# ESP_SCH_2_IMU.net
KiCad netlist of a schematic drawn in EasyEDA
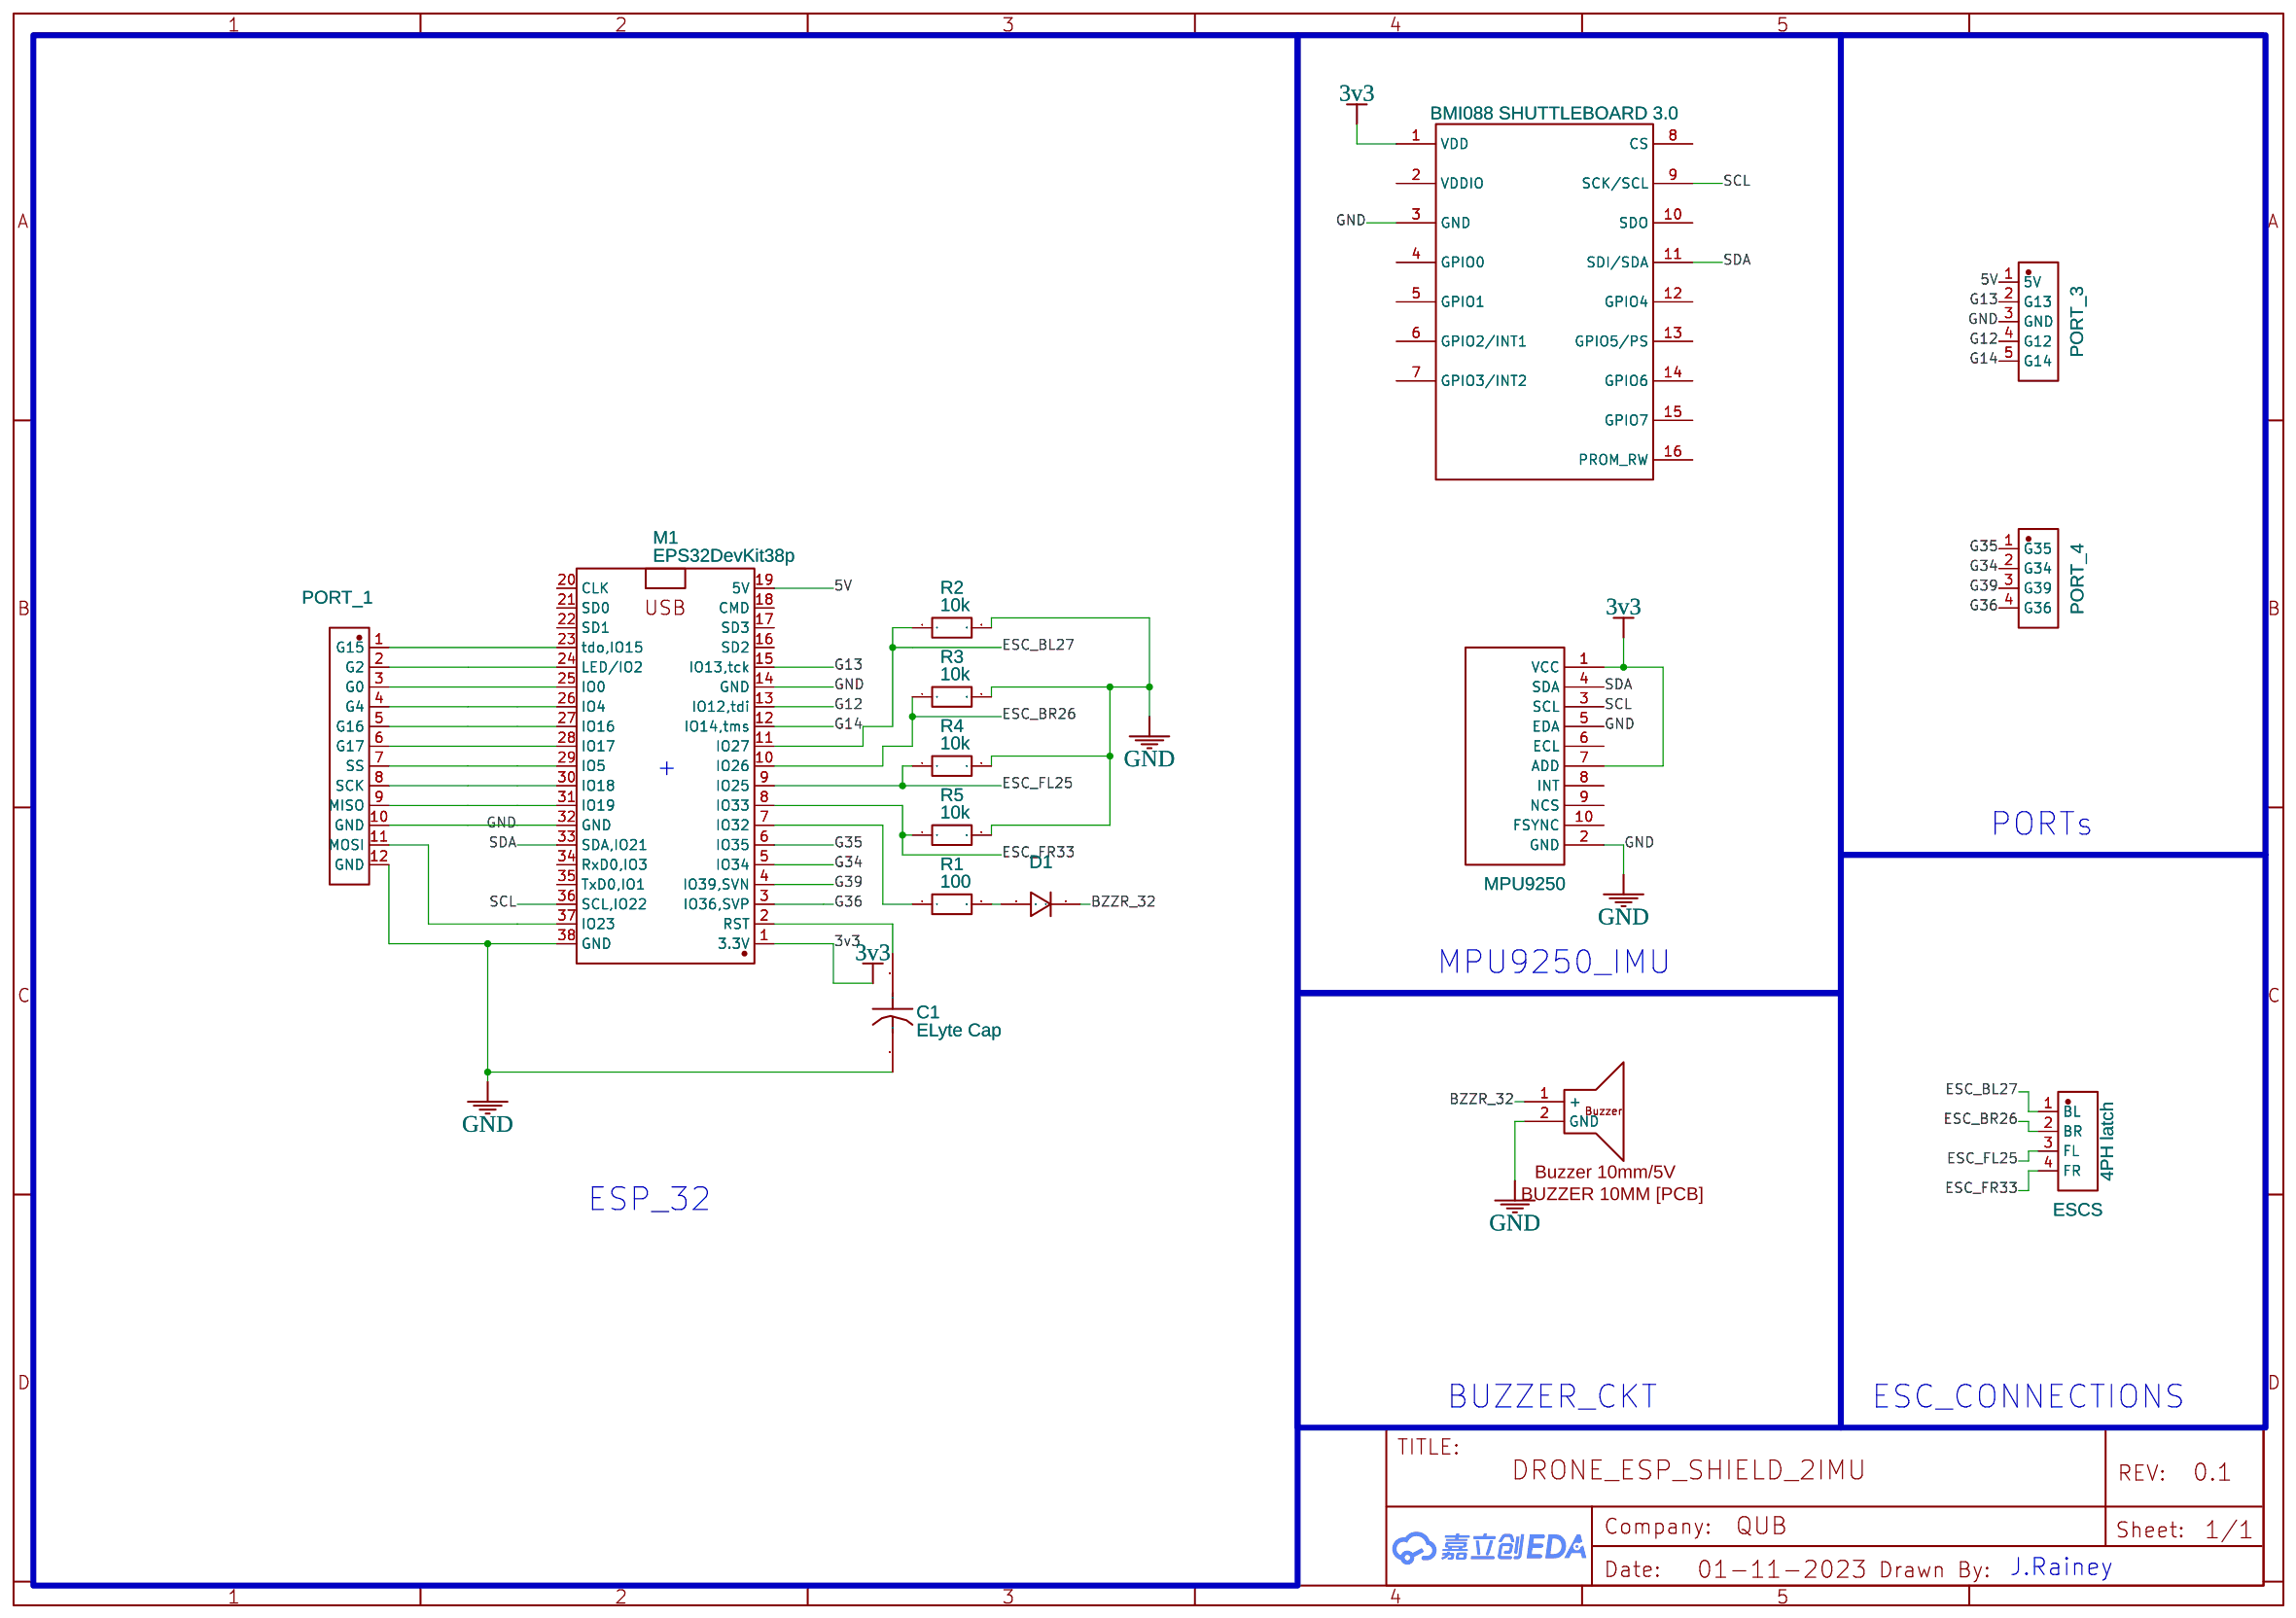
[diagram p0: schematic sheet]

(export (version "E")
  (design (tool "Eeschema 10.0.6"))
  (components
    (comp (ref "BUZZER")
      (value "Buzzer 10mm/5V")
      (fields (field (name "BOM_Manufacturer Part") "BUZZER"))
      (libsource (lib "") (part "Buzzer 10mm/5V"))
    )
    (comp (ref "C1") (value "ELyte Cap") (libsource (lib "") (part "Electrolitic Capacitor")))
    (comp (ref "D1")
      (value "1N4448")
      (fields (field (name "Manufacturer") "ST(先科)"))
      (libsource (lib "") (part "1N4448"))
    )
    (comp (ref "ESCS")
      (value "4PH latch")
      (fields
        (field (name "BOM_Manufacturer Part") "A2541HWV-4P")
        (field (name "BOM_Supplier Part") "C5176037")
      )
      (libsource (lib "") (part "A2541HWV-4P_C5176037"))
    )
    (comp (ref "M1") (value "EPS32DevKit38p") (libsource (lib "") (part "EPS32DevKit38p")))
    (comp (ref "MPU9250") (value "MPU9250") (libsource (lib "") (part "MPU9250 MODULE")))
    (comp (ref "PORT_1")
      (value "ZX-PM2.54-1-12PY")
      (fields (field (name "Manufacturer") "Megastar(兆星)"))
      (libsource (lib "") (part "ZX-PM2.54-1-12PY"))
    )
    (comp (ref "PORT_3")
      (value "PORT_3")
      (fields (field (name "Manufacturer Part") "DS1002-03-1x5131") (field (name "Manufacturer") "CONNFLY"))
      (libsource (lib "") (part "DS1002-03-1X5131"))
    )
    (comp (ref "PORT_4")
      (value "0022285044")
      (fields (field (name "BOM_Supplier Part") "C9900016049"))
      (libsource (lib "") (part "0022285044"))
    )
    (comp (ref "R1") (value "100") (libsource (lib "") (part "R_AXIAL-0.4_EU")))
    (comp (ref "R2") (value "10k") (libsource (lib "") (part "R_AXIAL-0.4_EU")))
    (comp (ref "R3") (value "10k") (libsource (lib "") (part "R_AXIAL-0.4_EU")))
    (comp (ref "R4") (value "10k") (libsource (lib "") (part "R_AXIAL-0.4_EU")))
    (comp (ref "R5") (value "10k") (libsource (lib "") (part "R_AXIAL-0.4_EU")))
    (comp (ref "U1")
      (value "BMI088 SHUTTLEBOARD 3.0")
      (fields
        (field (name "BOM_Manufacturer Part") "BHI260AP Shuttle Board 3.0")
        (field (name "BOM_Supplier Part") "262-SB3.0BHI260AP")
      )
      (libsource (lib "") (part "BMI088 SHUTTLEBOARD 3.0"))
    )
  )
  (nets
    (net (code "1") (name "/5V") (class "Default")
      (node (ref "M1") (pin "19") (pinfunction "5V_19") (pintype "unspecified"))
      (node (ref "PORT_3") (pin "1") (pinfunction "5V_1") (pintype "unspecified"))
    )
    (net (code "2") (name "/BZZR_32") (class "Default")
      (node (ref "BUZZER") (pin "1") (pinfunction "+_1") (pintype "unspecified"))
      (node (ref "D1") (pin "2") (pinfunction "K_2") (pintype "unspecified"))
    )
    (net (code "3") (name "/ESC_BL27") (class "Default")
      (node (ref "ESCS") (pin "1") (pinfunction "BL_1") (pintype "unspecified"))
      (node (ref "M1") (pin "11") (pinfunction "IO27_11") (pintype "unspecified"))
      (node (ref "R2") (pin "1") (pinfunction "1_1") (pintype "unspecified"))
    )
    (net (code "4") (name "/ESC_BR26") (class "Default")
      (node (ref "ESCS") (pin "2") (pinfunction "BR_2") (pintype "unspecified"))
      (node (ref "M1") (pin "10") (pinfunction "IO26_10") (pintype "unspecified"))
      (node (ref "R3") (pin "1") (pinfunction "1_1") (pintype "unspecified"))
    )
    (net (code "5") (name "/ESC_FL25") (class "Default")
      (node (ref "ESCS") (pin "3") (pinfunction "FL_3") (pintype "unspecified"))
      (node (ref "M1") (pin "9") (pinfunction "IO25_9") (pintype "unspecified"))
      (node (ref "R4") (pin "1") (pinfunction "1_1") (pintype "unspecified"))
    )
    (net (code "6") (name "/ESC_FR33") (class "Default")
      (node (ref "ESCS") (pin "4") (pinfunction "FR_4") (pintype "unspecified"))
      (node (ref "M1") (pin "8") (pinfunction "IO33_8") (pintype "unspecified"))
      (node (ref "R5") (pin "1") (pinfunction "1_1") (pintype "unspecified"))
    )
    (net (code "7") (name "/G12") (class "Default")
      (node (ref "M1") (pin "13") (pinfunction "IO12,tdi_13") (pintype "unspecified"))
      (node (ref "PORT_3") (pin "4") (pinfunction "G12_4") (pintype "unspecified"))
    )
    (net (code "8") (name "/G13") (class "Default")
      (node (ref "M1") (pin "15") (pinfunction "IO13,tck_15") (pintype "unspecified"))
      (node (ref "PORT_3") (pin "2") (pinfunction "G13_2") (pintype "unspecified"))
    )
    (net (code "9") (name "/G14") (class "Default")
      (node (ref "M1") (pin "12") (pinfunction "IO14,tms_12") (pintype "unspecified"))
      (node (ref "PORT_3") (pin "5") (pinfunction "G14_5") (pintype "unspecified"))
    )
    (net (code "10") (name "/G34") (class "Default")
      (node (ref "M1") (pin "5") (pinfunction "IO34_5") (pintype "unspecified"))
      (node (ref "PORT_4") (pin "2") (pinfunction "G34_2") (pintype "unspecified"))
    )
    (net (code "11") (name "/G35") (class "Default")
      (node (ref "M1") (pin "6") (pinfunction "IO35_6") (pintype "unspecified"))
      (node (ref "PORT_4") (pin "1") (pinfunction "G35_1") (pintype "unspecified"))
    )
    (net (code "12") (name "/G36") (class "Default")
      (node (ref "M1") (pin "3") (pinfunction "IO36,SVP_3") (pintype "unspecified"))
      (node (ref "PORT_4") (pin "4") (pinfunction "G36_4") (pintype "unspecified"))
    )
    (net (code "13") (name "/G39") (class "Default")
      (node (ref "M1") (pin "4") (pinfunction "IO39,SVN_4") (pintype "unspecified"))
      (node (ref "PORT_4") (pin "3") (pinfunction "G39_3") (pintype "unspecified"))
    )
    (net (code "14") (name "/SCL") (class "Default")
      (node (ref "M1") (pin "36") (pinfunction "SCL,IO22_36") (pintype "unspecified"))
      (node (ref "MPU9250") (pin "3") (pinfunction "SCL_3") (pintype "bidirectional"))
      (node (ref "U1") (pin "9") (pinfunction "SCK/SCL_9") (pintype "unspecified"))
    )
    (net (code "15") (name "/SDA") (class "Default")
      (node (ref "M1") (pin "33") (pinfunction "SDA,IO21_33") (pintype "unspecified"))
      (node (ref "MPU9250") (pin "4") (pinfunction "SDA_4") (pintype "bidirectional"))
      (node (ref "U1") (pin "11") (pinfunction "SDI/SDA_11") (pintype "unspecified"))
    )
    (net (code "16") (name "3v3") (class "Default")
      (node (ref "M1") (pin "1") (pinfunction "3.3V_1") (pintype "unspecified"))
      (node (ref "MPU9250") (pin "1") (pinfunction "VCC_1") (pintype "passive"))
      (node (ref "MPU9250") (pin "7") (pinfunction "ADD_7") (pintype "bidirectional"))
      (node (ref "U1") (pin "1") (pinfunction "VDD_1") (pintype "unspecified"))
    )
    (net (code "17") (name "GND") (class "Default")
      (node (ref "BUZZER") (pin "2") (pinfunction "GND_2") (pintype "unspecified"))
      (node (ref "C1") (pin "2") (pinfunction "2_2") (pintype "unspecified"))
      (node (ref "M1") (pin "14") (pinfunction "GND_14") (pintype "unspecified"))
      (node (ref "M1") (pin "32") (pinfunction "GND_32") (pintype "unspecified"))
      (node (ref "M1") (pin "38") (pinfunction "GND_38") (pintype "unspecified"))
      (node (ref "MPU9250") (pin "2") (pinfunction "GND_2") (pintype "passive"))
      (node (ref "MPU9250") (pin "5") (pinfunction "EDA_5") (pintype "bidirectional"))
      (node (ref "PORT_1") (pin "10") (pinfunction "GND_10") (pintype "unspecified"))
      (node (ref "PORT_1") (pin "12") (pinfunction "GND_12") (pintype "unspecified"))
      (node (ref "PORT_3") (pin "3") (pinfunction "GND_3") (pintype "unspecified"))
      (node (ref "R2") (pin "2") (pinfunction "2_2") (pintype "unspecified"))
      (node (ref "R3") (pin "2") (pinfunction "2_2") (pintype "unspecified"))
      (node (ref "R4") (pin "2") (pinfunction "2_2") (pintype "unspecified"))
      (node (ref "R5") (pin "2") (pinfunction "2_2") (pintype "unspecified"))
      (node (ref "U1") (pin "3") (pinfunction "GND_3") (pintype "unspecified"))
    )
    (net (code "18") (name "Net-(D1-A)") (class "Default")
      (node (ref "D1") (pin "1") (pinfunction "A_1") (pintype "unspecified"))
      (node (ref "R1") (pin "2") (pinfunction "2_2") (pintype "unspecified"))
    )
    (net (code "19") (name "Net-(M1-IO0)") (class "Default")
      (node (ref "M1") (pin "25") (pinfunction "IO0_25") (pintype "unspecified"))
      (node (ref "PORT_1") (pin "3") (pinfunction "G0_3") (pintype "unspecified"))
    )
    (net (code "20") (name "Net-(M1-IO4)") (class "Default")
      (node (ref "M1") (pin "26") (pinfunction "IO4_26") (pintype "unspecified"))
      (node (ref "PORT_1") (pin "4") (pinfunction "G4_4") (pintype "unspecified"))
    )
    (net (code "21") (name "Net-(M1-IO5)") (class "Default")
      (node (ref "M1") (pin "29") (pinfunction "IO5_29") (pintype "unspecified"))
      (node (ref "PORT_1") (pin "7") (pinfunction "SS_7") (pintype "unspecified"))
    )
    (net (code "22") (name "Net-(M1-IO16)") (class "Default")
      (node (ref "M1") (pin "27") (pinfunction "IO16_27") (pintype "unspecified"))
      (node (ref "PORT_1") (pin "5") (pinfunction "G16_5") (pintype "unspecified"))
    )
    (net (code "23") (name "Net-(M1-IO17)") (class "Default")
      (node (ref "M1") (pin "28") (pinfunction "IO17_28") (pintype "unspecified"))
      (node (ref "PORT_1") (pin "6") (pinfunction "G17_6") (pintype "unspecified"))
    )
    (net (code "24") (name "Net-(M1-IO18)") (class "Default")
      (node (ref "M1") (pin "30") (pinfunction "IO18_30") (pintype "unspecified"))
      (node (ref "PORT_1") (pin "8") (pinfunction "SCK_8") (pintype "unspecified"))
    )
    (net (code "25") (name "Net-(M1-IO19)") (class "Default")
      (node (ref "M1") (pin "31") (pinfunction "IO19_31") (pintype "unspecified"))
      (node (ref "PORT_1") (pin "9") (pinfunction "MISO_9") (pintype "unspecified"))
    )
    (net (code "26") (name "Net-(M1-IO23)") (class "Default")
      (node (ref "M1") (pin "37") (pinfunction "IO23_37") (pintype "unspecified"))
      (node (ref "PORT_1") (pin "11") (pinfunction "MOSI_11") (pintype "unspecified"))
    )
    (net (code "27") (name "Net-(M1-IO32)") (class "Default")
      (node (ref "M1") (pin "7") (pinfunction "IO32_7") (pintype "unspecified"))
      (node (ref "R1") (pin "1") (pinfunction "1_1") (pintype "unspecified"))
    )
    (net (code "28") (name "Net-(M1-LED{slash}IO2)") (class "Default")
      (node (ref "M1") (pin "24") (pinfunction "LED/IO2_24") (pintype "unspecified"))
      (node (ref "PORT_1") (pin "2") (pinfunction "G2_2") (pintype "unspecified"))
    )
    (net (code "29") (name "Net-(M1-RST)") (class "Default")
      (node (ref "C1") (pin "1") (pinfunction "1_1") (pintype "unspecified"))
      (node (ref "M1") (pin "2") (pinfunction "RST_2") (pintype "unspecified"))
    )
    (net (code "30") (name "Net-(M1-tdo,IO15)") (class "Default")
      (node (ref "M1") (pin "23") (pinfunction "tdo,IO15_23") (pintype "unspecified"))
      (node (ref "PORT_1") (pin "1") (pinfunction "G15_1") (pintype "unspecified"))
    )
    (net (code "31") (name "unconnected-(M1-CLK-Pad20)") (class "Default")
      (node (ref "M1") (pin "20") (pinfunction "CLK_20") (pintype "unspecified"))
    )
    (net (code "32") (name "unconnected-(M1-CMD-Pad18)") (class "Default")
      (node (ref "M1") (pin "18") (pinfunction "CMD_18") (pintype "unspecified"))
    )
    (net (code "33") (name "unconnected-(M1-RxD0,IO3-Pad34)") (class "Default")
      (node (ref "M1") (pin "34") (pinfunction "RxD0,IO3_34") (pintype "unspecified"))
    )
    (net (code "34") (name "unconnected-(M1-SD0-Pad21)") (class "Default")
      (node (ref "M1") (pin "21") (pinfunction "SD0_21") (pintype "unspecified"))
    )
    (net (code "35") (name "unconnected-(M1-SD1-Pad22)") (class "Default")
      (node (ref "M1") (pin "22") (pinfunction "SD1_22") (pintype "unspecified"))
    )
    (net (code "36") (name "unconnected-(M1-SD2-Pad16)") (class "Default")
      (node (ref "M1") (pin "16") (pinfunction "SD2_16") (pintype "unspecified"))
    )
    (net (code "37") (name "unconnected-(M1-SD3-Pad17)") (class "Default")
      (node (ref "M1") (pin "17") (pinfunction "SD3_17") (pintype "unspecified"))
    )
    (net (code "38") (name "unconnected-(M1-TxD0,IO1-Pad35)") (class "Default")
      (node (ref "M1") (pin "35") (pinfunction "TxD0,IO1_35") (pintype "unspecified"))
    )
    (net (code "39") (name "unconnected-(MPU9250-ECL-Pad6)") (class "Default")
      (node (ref "MPU9250") (pin "6") (pinfunction "ECL_6") (pintype "bidirectional"))
    )
    (net (code "40") (name "unconnected-(MPU9250-FSYNC-Pad10)") (class "Default")
      (node (ref "MPU9250") (pin "10") (pinfunction "FSYNC_10") (pintype "bidirectional"))
    )
    (net (code "41") (name "unconnected-(MPU9250-INT-Pad8)") (class "Default")
      (node (ref "MPU9250") (pin "8") (pinfunction "INT_8") (pintype "bidirectional"))
    )
    (net (code "42") (name "unconnected-(MPU9250-NCS-Pad9)") (class "Default")
      (node (ref "MPU9250") (pin "9") (pinfunction "NCS_9") (pintype "bidirectional"))
    )
    (net (code "43") (name "unconnected-(U1-CS-Pad8)") (class "Default")
      (node (ref "U1") (pin "8") (pinfunction "CS_8") (pintype "unspecified"))
    )
    (net (code "44") (name "unconnected-(U1-GPIO0-Pad4)") (class "Default")
      (node (ref "U1") (pin "4") (pinfunction "GPIO0_4") (pintype "unspecified"))
    )
    (net (code "45") (name "unconnected-(U1-GPIO1-Pad5)") (class "Default")
      (node (ref "U1") (pin "5") (pinfunction "GPIO1_5") (pintype "unspecified"))
    )
    (net (code "46") (name "unconnected-(U1-GPIO2{slash}INT1-Pad6)") (class "Default")
      (node (ref "U1") (pin "6") (pinfunction "GPIO2/INT1_6") (pintype "unspecified"))
    )
    (net (code "47") (name "unconnected-(U1-GPIO3{slash}INT2-Pad7)") (class "Default")
      (node (ref "U1") (pin "7") (pinfunction "GPIO3/INT2_7") (pintype "unspecified"))
    )
    (net (code "48") (name "unconnected-(U1-GPIO4-Pad12)") (class "Default")
      (node (ref "U1") (pin "12") (pinfunction "GPIO4_12") (pintype "unspecified"))
    )
    (net (code "49") (name "unconnected-(U1-GPIO5{slash}PS-Pad13)") (class "Default")
      (node (ref "U1") (pin "13") (pinfunction "GPIO5/PS_13") (pintype "unspecified"))
    )
    (net (code "50") (name "unconnected-(U1-GPIO6-Pad14)") (class "Default")
      (node (ref "U1") (pin "14") (pinfunction "GPIO6_14") (pintype "unspecified"))
    )
    (net (code "51") (name "unconnected-(U1-GPIO7-Pad15)") (class "Default")
      (node (ref "U1") (pin "15") (pinfunction "GPIO7_15") (pintype "unspecified"))
    )
    (net (code "52") (name "unconnected-(U1-PROM_RW-Pad16)") (class "Default")
      (node (ref "U1") (pin "16") (pinfunction "PROM_RW_16") (pintype "unspecified"))
    )
    (net (code "53") (name "unconnected-(U1-SDO-Pad10)") (class "Default")
      (node (ref "U1") (pin "10") (pinfunction "SDO_10") (pintype "unspecified"))
    )
    (net (code "54") (name "unconnected-(U1-VDDIO-Pad2)") (class "Default")
      (node (ref "U1") (pin "2") (pinfunction "VDDIO_2") (pintype "unspecified"))
    )
  )
)
